# Spectacle_Button_Board.net
KiCad netlist of a schematic drawn in EAGLE
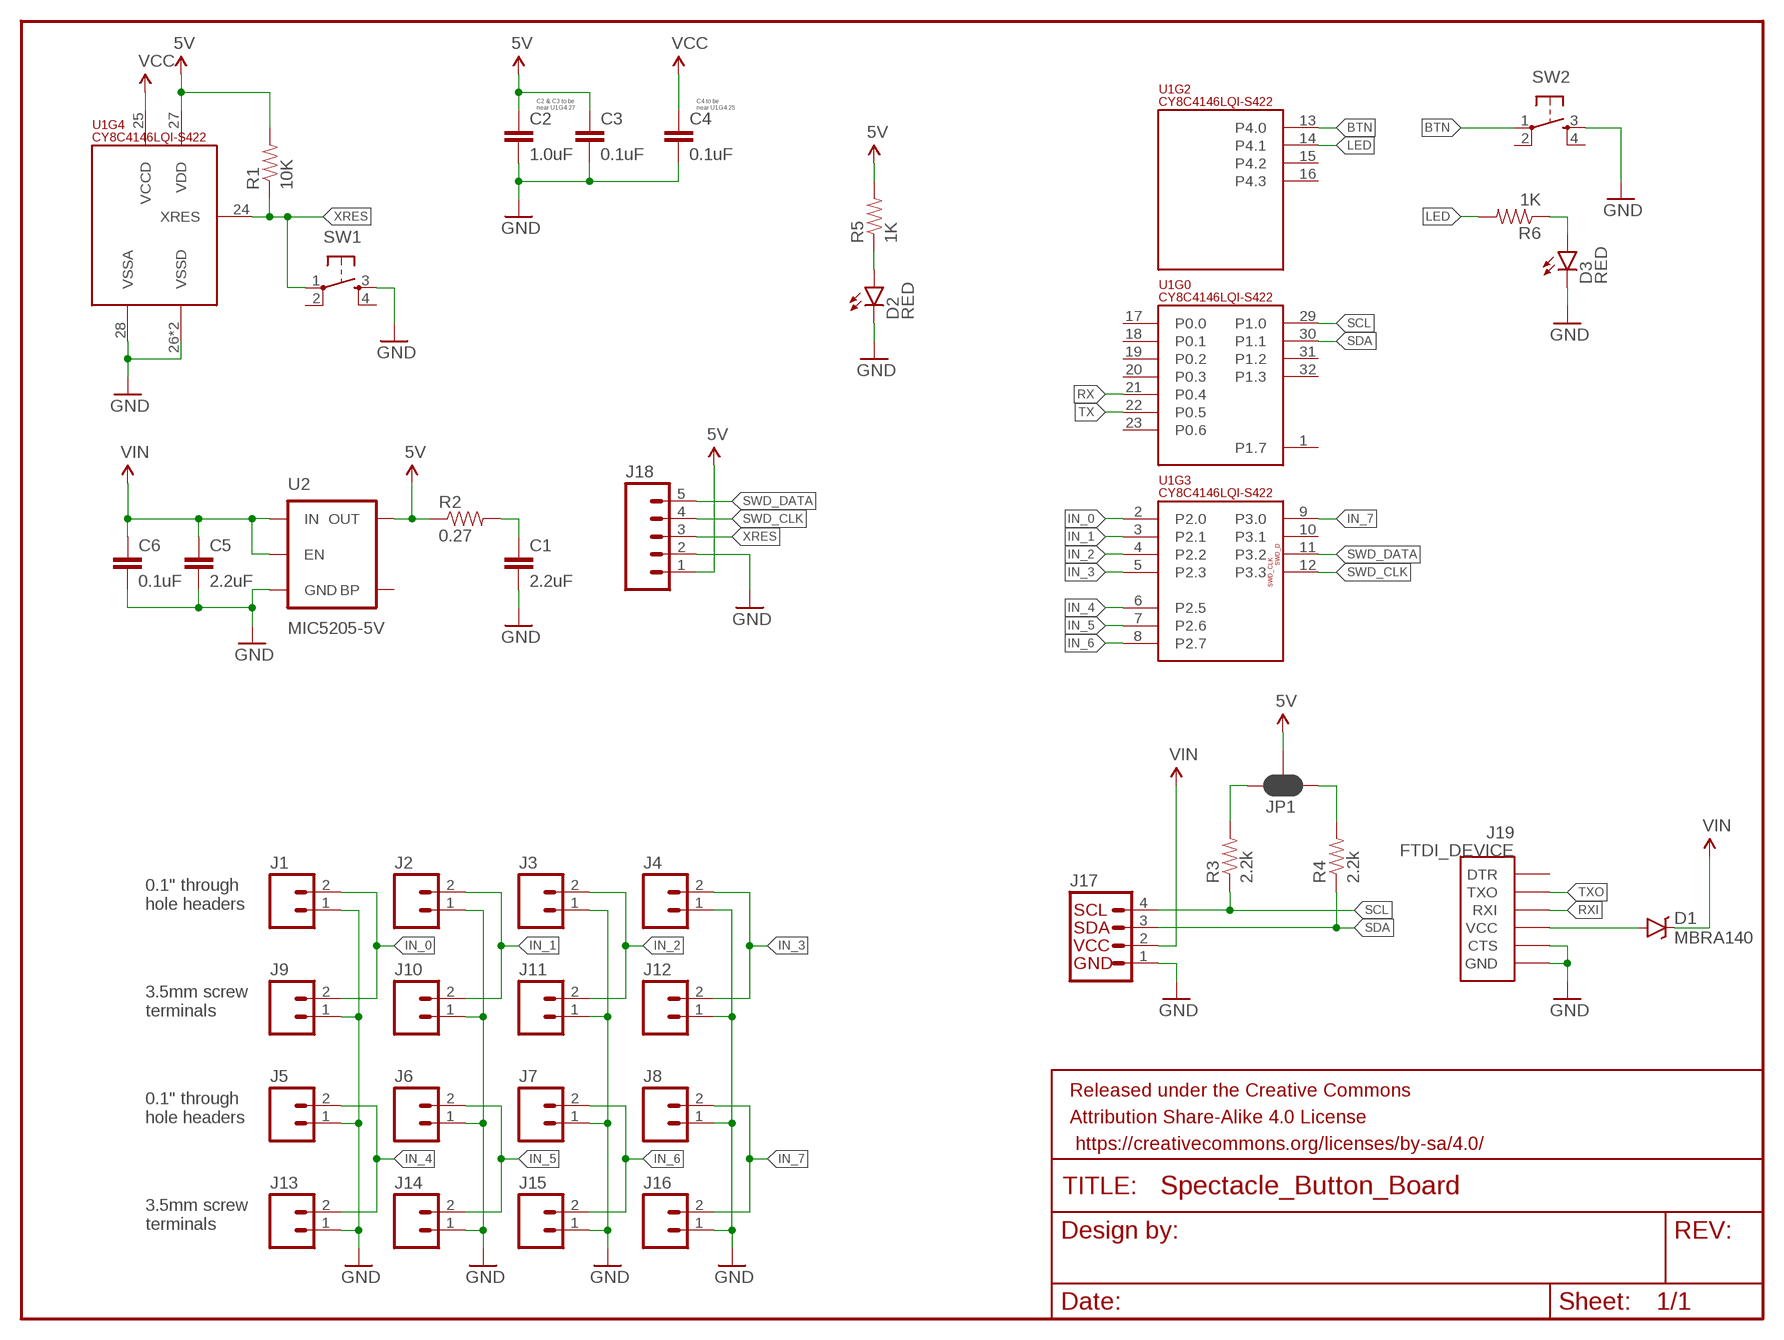
[diagram p0: schematic, sheet 1]

(export (version "E")
  (design (tool "Eeschema 10.0.6"))
  (components
    (comp (ref "C1")
      (value "2.2uF")
      (footprint "eagle-import:0603-CAP")
      (libsource (lib "eagle-import") (part "2.2UF-10V-20%(0603)"))
    )
    (comp (ref "C2")
      (value "1.0uF")
      (footprint "eagle-import:0402-CAP")
      (libsource (lib "eagle-import") (part "1.0UF-16V-10%(0402)"))
    )
    (comp (ref "C3")
      (value "0.1uF")
      (footprint "eagle-import:0402-CAP")
      (libsource (lib "eagle-import") (part "0.1UF-16V(+-10%)(0402)"))
    )
    (comp (ref "C4")
      (value "0.1uF")
      (footprint "eagle-import:0402-CAP")
      (libsource (lib "eagle-import") (part "0.1UF-16V(+-10%)(0402)"))
    )
    (comp (ref "C5")
      (value "2.2uF")
      (footprint "eagle-import:0603-CAP")
      (libsource (lib "eagle-import") (part "2.2UF-10V-20%(0603)"))
    )
    (comp (ref "C6")
      (value "0.1uF")
      (footprint "eagle-import:0402-CAP")
      (libsource (lib "eagle-import") (part "0.1UF-16V(+-10%)(0402)"))
    )
    (comp (ref "D1")
      (value "MBRA140")
      (footprint "eagle-import:SMA-DIODE")
      (libsource (lib "eagle-import") (part "DIODE-SCHOTTKY-MBRA140"))
    )
    (comp (ref "D2")
      (value "RED")
      (footprint "eagle-import:LED-0603")
      (libsource (lib "eagle-import") (part "LED-RED0603"))
    )
    (comp (ref "D3")
      (value "RED")
      (footprint "eagle-import:LED-0603")
      (libsource (lib "eagle-import") (part "LED-RED0603"))
    )
    (comp (ref "FRAME1")
      (value "FRAME-LETTER")
      (footprint "eagle-import:CREATIVE_COMMONS")
      (libsource (lib "eagle-import") (part "FRAME-LETTER"))
    )
    (comp (ref "J1")
      (value "M02PTH")
      (footprint "eagle-import:1X02")
      (libsource (lib "eagle-import") (part "M02PTH"))
    )
    (comp (ref "J2")
      (value "M02PTH")
      (footprint "eagle-import:1X02")
      (libsource (lib "eagle-import") (part "M02PTH"))
    )
    (comp (ref "J3")
      (value "M02PTH")
      (footprint "eagle-import:1X02")
      (libsource (lib "eagle-import") (part "M02PTH"))
    )
    (comp (ref "J4")
      (value "M02PTH")
      (footprint "eagle-import:1X02")
      (libsource (lib "eagle-import") (part "M02PTH"))
    )
    (comp (ref "J5")
      (value "M02PTH")
      (footprint "eagle-import:1X02")
      (libsource (lib "eagle-import") (part "M02PTH"))
    )
    (comp (ref "J6")
      (value "M02PTH")
      (footprint "eagle-import:1X02")
      (libsource (lib "eagle-import") (part "M02PTH"))
    )
    (comp (ref "J7")
      (value "M02PTH")
      (footprint "eagle-import:1X02")
      (libsource (lib "eagle-import") (part "M02PTH"))
    )
    (comp (ref "J8")
      (value "M02PTH")
      (footprint "eagle-import:1X02")
      (libsource (lib "eagle-import") (part "M02PTH"))
    )
    (comp (ref "J9")
      (value "M023.5MM_LOCK")
      (footprint "eagle-import:SCREWTERMINAL-3.5MM-2_LOCK")
      (libsource (lib "eagle-import") (part "M023.5MM_LOCK"))
    )
    (comp (ref "J10")
      (value "M023.5MM_LOCK")
      (footprint "eagle-import:SCREWTERMINAL-3.5MM-2_LOCK")
      (libsource (lib "eagle-import") (part "M023.5MM_LOCK"))
    )
    (comp (ref "J11")
      (value "M023.5MM_LOCK")
      (footprint "eagle-import:SCREWTERMINAL-3.5MM-2_LOCK")
      (libsource (lib "eagle-import") (part "M023.5MM_LOCK"))
    )
    (comp (ref "J12")
      (value "M023.5MM_LOCK")
      (footprint "eagle-import:SCREWTERMINAL-3.5MM-2_LOCK")
      (libsource (lib "eagle-import") (part "M023.5MM_LOCK"))
    )
    (comp (ref "J13")
      (value "M023.5MM_LOCK")
      (footprint "eagle-import:SCREWTERMINAL-3.5MM-2_LOCK")
      (libsource (lib "eagle-import") (part "M023.5MM_LOCK"))
    )
    (comp (ref "J14")
      (value "M023.5MM_LOCK")
      (footprint "eagle-import:SCREWTERMINAL-3.5MM-2_LOCK")
      (libsource (lib "eagle-import") (part "M023.5MM_LOCK"))
    )
    (comp (ref "J15")
      (value "M023.5MM_LOCK")
      (footprint "eagle-import:SCREWTERMINAL-3.5MM-2_LOCK")
      (libsource (lib "eagle-import") (part "M023.5MM_LOCK"))
    )
    (comp (ref "J16")
      (value "M023.5MM_LOCK")
      (footprint "eagle-import:SCREWTERMINAL-3.5MM-2_LOCK")
      (libsource (lib "eagle-import") (part "M023.5MM_LOCK"))
    )
    (comp (ref "J17")
      (value "I2C_STANDARD")
      (footprint "eagle-import:1X04")
      (libsource (lib "eagle-import") (part "I2C_STANDARD"))
    )
    (comp (ref "J18")
      (value "M05PTH")
      (footprint "eagle-import:1X05")
      (libsource (lib "eagle-import") (part "M05PTH"))
    )
    (comp (ref "J19")
      (value "FTDI_DEVICE")
      (footprint "eagle-import:FTDI_DEVICE_SIDE")
      (libsource (lib "eagle-import") (part "FTDI_DEVICE"))
    )
    (comp (ref "JP1")
      (value "JUMPER-PAD-3-NC_BY_PASTE")
      (footprint "eagle-import:PAD-JUMPER-3-NC_BY_PASTE_YES_SILK_FULL_BOX")
      (libsource (lib "eagle-import") (part "JUMPER-PAD-3-NC_BY_PASTE"))
    )
    (comp (ref "R1")
      (value "10K")
      (footprint "eagle-import:0603-RES")
      (libsource (lib "eagle-import") (part "10KOHM-1/10W-1%(0603)0603"))
    )
    (comp (ref "R2")
      (value "0.27")
      (footprint "eagle-import:0603-RES")
      (libsource (lib "eagle-import") (part "0.27OHM-1/10W-1%(0603)"))
    )
    (comp (ref "R3")
      (value "2.2k")
      (footprint "eagle-import:0603-RES")
      (libsource (lib "eagle-import") (part "2.2KOHM-1/10W-1%(0603)"))
    )
    (comp (ref "R4")
      (value "2.2k")
      (footprint "eagle-import:0603-RES")
      (libsource (lib "eagle-import") (part "2.2KOHM-1/10W-1%(0603)"))
    )
    (comp (ref "R5")
      (value "1K")
      (footprint "eagle-import:0603-RES")
      (libsource (lib "eagle-import") (part "1KOHM-1/10W-1%(0603)"))
    )
    (comp (ref "R6")
      (value "1K")
      (footprint "eagle-import:0603-RES")
      (libsource (lib "eagle-import") (part "1KOHM-1/10W-1%(0603)"))
    )
    (comp (ref "SW1")
      (value "SWITCH_SPST_4_PINRECT")
      (footprint "eagle-import:TACTILE_SWITCH_SMD_4.6X2.8MM")
      (libsource (lib "eagle-import") (part "SWITCH_SPST_4_PINRECT"))
    )
    (comp (ref "SW2")
      (value "SWITCH_SPST_4_PINRECT")
      (footprint "eagle-import:TACTILE_SWITCH_SMD_4.6X2.8MM")
      (libsource (lib "eagle-import") (part "SWITCH_SPST_4_PINRECT"))
    )
    (comp (ref "U1")
      (value "CY8C4146LQI-S422")
      (footprint "eagle-import:QFN-32")
      (libsource (lib "eagle-import") (part "PSOC4_4100S_32QFN"))
    )
    (comp (ref "U2")
      (value "MIC5205-5V")
      (footprint "eagle-import:SOT23-5")
      (libsource (lib "eagle-import") (part "V_REG_MIC52055V"))
    )
  )
  (nets
    (net (code "1") (name "5V") (class "Default")
      (node (ref "C2") (pin "1") (pinfunction "1_1") (pintype "passive"))
      (node (ref "C3") (pin "1") (pinfunction "1_1") (pintype "passive"))
      (node (ref "J18") (pin "1") (pinfunction "1_1") (pintype "passive"))
      (node (ref "JP1") (pin "2") (pinfunction "2_2") (pintype "passive"))
      (node (ref "R1") (pin "2") (pinfunction "2_2") (pintype "passive"))
      (node (ref "R2") (pin "1") (pinfunction "1_1") (pintype "passive"))
      (node (ref "R5") (pin "2") (pinfunction "2_2") (pintype "passive"))
      (node (ref "U1") (pin "27") (pinfunction "VDD_27") (pintype "bidirectional"))
      (node (ref "U2") (pin "5") (pinfunction "OUT_5") (pintype "passive"))
    )
    (net (code "2") (name "BTN") (class "Default")
      (node (ref "SW2") (pin "1") (pinfunction "1_1") (pintype "passive"))
      (node (ref "U1") (pin "13") (pinfunction "P4.0_13") (pintype "bidirectional"))
    )
    (net (code "3") (name "GND") (class "Default")
      (node (ref "C1") (pin "2") (pinfunction "2_2") (pintype "passive"))
      (node (ref "C2") (pin "2") (pinfunction "2_2") (pintype "passive"))
      (node (ref "C3") (pin "2") (pinfunction "2_2") (pintype "passive"))
      (node (ref "C4") (pin "2") (pinfunction "2_2") (pintype "passive"))
      (node (ref "C5") (pin "2") (pinfunction "2_2") (pintype "passive"))
      (node (ref "C6") (pin "2") (pinfunction "2_2") (pintype "passive"))
      (node (ref "D2") (pin "C") (pinfunction "C_C") (pintype "passive"))
      (node (ref "D3") (pin "C") (pinfunction "C_C") (pintype "passive"))
      (node (ref "J1") (pin "1") (pinfunction "1_1") (pintype "passive"))
      (node (ref "J10") (pin "1") (pinfunction "1_1") (pintype "passive"))
      (node (ref "J11") (pin "1") (pinfunction "1_1") (pintype "passive"))
      (node (ref "J12") (pin "1") (pinfunction "1_1") (pintype "passive"))
      (node (ref "J13") (pin "1") (pinfunction "1_1") (pintype "passive"))
      (node (ref "J14") (pin "1") (pinfunction "1_1") (pintype "passive"))
      (node (ref "J15") (pin "1") (pinfunction "1_1") (pintype "passive"))
      (node (ref "J16") (pin "1") (pinfunction "1_1") (pintype "passive"))
      (node (ref "J17") (pin "1") (pinfunction "1_1") (pintype "passive"))
      (node (ref "J18") (pin "2") (pinfunction "2_2") (pintype "passive"))
      (node (ref "J19") (pin "P$5") (pinfunction "CTS_P$5") (pintype "bidirectional"))
      (node (ref "J19") (pin "P$6") (pinfunction "GND_P$6") (pintype "bidirectional"))
      (node (ref "J2") (pin "1") (pinfunction "1_1") (pintype "passive"))
      (node (ref "J3") (pin "1") (pinfunction "1_1") (pintype "passive"))
      (node (ref "J4") (pin "1") (pinfunction "1_1") (pintype "passive"))
      (node (ref "J5") (pin "1") (pinfunction "1_1") (pintype "passive"))
      (node (ref "J6") (pin "1") (pinfunction "1_1") (pintype "passive"))
      (node (ref "J7") (pin "1") (pinfunction "1_1") (pintype "passive"))
      (node (ref "J8") (pin "1") (pinfunction "1_1") (pintype "passive"))
      (node (ref "J9") (pin "1") (pinfunction "1_1") (pintype "passive"))
      (node (ref "SW1") (pin "3") (pinfunction "3_3") (pintype "passive"))
      (node (ref "SW2") (pin "3") (pinfunction "3_3") (pintype "passive"))
      (node (ref "U1") (pin "26") (pinfunction "VSSD_26") (pintype "bidirectional"))
      (node (ref "U1") (pin "28") (pinfunction "VSSA_28") (pintype "bidirectional"))
      (node (ref "U1") (pin "EP") (pinfunction "VSSD_EP") (pintype "bidirectional"))
      (node (ref "U2") (pin "2") (pinfunction "GND_2") (pintype "input"))
    )
    (net (code "4") (name "IN_0") (class "Default")
      (node (ref "J1") (pin "2") (pinfunction "2_2") (pintype "passive"))
      (node (ref "J9") (pin "2") (pinfunction "2_2") (pintype "passive"))
      (node (ref "U1") (pin "2") (pinfunction "P2.0_2") (pintype "bidirectional"))
    )
    (net (code "5") (name "IN_1") (class "Default")
      (node (ref "J10") (pin "2") (pinfunction "2_2") (pintype "passive"))
      (node (ref "J2") (pin "2") (pinfunction "2_2") (pintype "passive"))
      (node (ref "U1") (pin "3") (pinfunction "P2.1_3") (pintype "bidirectional"))
    )
    (net (code "6") (name "IN_2") (class "Default")
      (node (ref "J11") (pin "2") (pinfunction "2_2") (pintype "passive"))
      (node (ref "J3") (pin "2") (pinfunction "2_2") (pintype "passive"))
      (node (ref "U1") (pin "4") (pinfunction "P2.2_4") (pintype "bidirectional"))
    )
    (net (code "7") (name "IN_3") (class "Default")
      (node (ref "J12") (pin "2") (pinfunction "2_2") (pintype "passive"))
      (node (ref "J4") (pin "2") (pinfunction "2_2") (pintype "passive"))
      (node (ref "U1") (pin "5") (pinfunction "P2.3_5") (pintype "bidirectional"))
    )
    (net (code "8") (name "IN_4") (class "Default")
      (node (ref "J13") (pin "2") (pinfunction "2_2") (pintype "passive"))
      (node (ref "J5") (pin "2") (pinfunction "2_2") (pintype "passive"))
      (node (ref "U1") (pin "6") (pinfunction "P2.5_6") (pintype "bidirectional"))
    )
    (net (code "9") (name "IN_5") (class "Default")
      (node (ref "J14") (pin "2") (pinfunction "2_2") (pintype "passive"))
      (node (ref "J6") (pin "2") (pinfunction "2_2") (pintype "passive"))
      (node (ref "U1") (pin "7") (pinfunction "P2.6_7") (pintype "bidirectional"))
    )
    (net (code "10") (name "IN_6") (class "Default")
      (node (ref "J15") (pin "2") (pinfunction "2_2") (pintype "passive"))
      (node (ref "J7") (pin "2") (pinfunction "2_2") (pintype "passive"))
      (node (ref "U1") (pin "8") (pinfunction "P2.7_8") (pintype "bidirectional"))
    )
    (net (code "11") (name "IN_7") (class "Default")
      (node (ref "J16") (pin "2") (pinfunction "2_2") (pintype "passive"))
      (node (ref "J8") (pin "2") (pinfunction "2_2") (pintype "passive"))
      (node (ref "U1") (pin "9") (pinfunction "P3.0_9") (pintype "bidirectional"))
    )
    (net (code "12") (name "LED") (class "Default")
      (node (ref "R6") (pin "2") (pinfunction "2_2") (pintype "passive"))
      (node (ref "U1") (pin "14") (pinfunction "P4.1_14") (pintype "bidirectional"))
    )
    (net (code "13") (name "Net-(C1-Pad1)") (class "Default")
      (node (ref "C1") (pin "1") (pinfunction "1_1") (pintype "passive"))
      (node (ref "R2") (pin "2") (pinfunction "2_2") (pintype "passive"))
    )
    (net (code "14") (name "Net-(D2-PadA)") (class "Default")
      (node (ref "D2") (pin "A") (pinfunction "A_A") (pintype "passive"))
      (node (ref "R5") (pin "1") (pinfunction "1_1") (pintype "passive"))
    )
    (net (code "15") (name "Net-(D3-PadA)") (class "Default")
      (node (ref "D3") (pin "A") (pinfunction "A_A") (pintype "passive"))
      (node (ref "R6") (pin "1") (pinfunction "1_1") (pintype "passive"))
    )
    (net (code "16") (name "Net-(J19-VCC)") (class "Default")
      (node (ref "D1") (pin "A") (pinfunction "A_A") (pintype "passive"))
      (node (ref "J19") (pin "P$4") (pinfunction "VCC_P$4") (pintype "bidirectional"))
    )
    (net (code "17") (name "Net-(JP1-Pad1)") (class "Default")
      (node (ref "JP1") (pin "1") (pinfunction "1_1") (pintype "passive"))
      (node (ref "R4") (pin "2") (pinfunction "2_2") (pintype "passive"))
    )
    (net (code "18") (name "Net-(JP1-Pad3)") (class "Default")
      (node (ref "JP1") (pin "3") (pinfunction "3_3") (pintype "passive"))
      (node (ref "R3") (pin "2") (pinfunction "2_2") (pintype "passive"))
    )
    (net (code "19") (name "RX") (class "Default")
      (node (ref "U1") (pin "21") (pinfunction "P0.4_21") (pintype "bidirectional"))
    )
    (net (code "20") (name "RXI") (class "Default")
      (node (ref "J19") (pin "P$3") (pinfunction "RXI_P$3") (pintype "bidirectional"))
    )
    (net (code "21") (name "SCL") (class "Default")
      (node (ref "J17") (pin "4") (pinfunction "4_4") (pintype "passive"))
      (node (ref "R3") (pin "1") (pinfunction "1_1") (pintype "passive"))
      (node (ref "U1") (pin "29") (pinfunction "P1.0_29") (pintype "bidirectional"))
    )
    (net (code "22") (name "SDA") (class "Default")
      (node (ref "J17") (pin "3") (pinfunction "3_3") (pintype "passive"))
      (node (ref "R4") (pin "1") (pinfunction "1_1") (pintype "passive"))
      (node (ref "U1") (pin "30") (pinfunction "P1.1_30") (pintype "bidirectional"))
    )
    (net (code "23") (name "SWD_CLK") (class "Default")
      (node (ref "J18") (pin "4") (pinfunction "4_4") (pintype "passive"))
      (node (ref "U1") (pin "12") (pinfunction "P3.3_12") (pintype "bidirectional"))
    )
    (net (code "24") (name "SWD_DATA") (class "Default")
      (node (ref "J18") (pin "5") (pinfunction "5_5") (pintype "passive"))
      (node (ref "U1") (pin "11") (pinfunction "P3.2_11") (pintype "bidirectional"))
    )
    (net (code "25") (name "TX") (class "Default")
      (node (ref "U1") (pin "22") (pinfunction "P0.5_22") (pintype "bidirectional"))
    )
    (net (code "26") (name "TXO") (class "Default")
      (node (ref "J19") (pin "P$2") (pinfunction "TXO_P$2") (pintype "bidirectional"))
    )
    (net (code "27") (name "VCC") (class "Default")
      (node (ref "C4") (pin "1") (pinfunction "1_1") (pintype "passive"))
      (node (ref "U1") (pin "25") (pinfunction "VCCD_25") (pintype "bidirectional"))
    )
    (net (code "28") (name "VIN") (class "Default")
      (node (ref "C5") (pin "1") (pinfunction "1_1") (pintype "passive"))
      (node (ref "C6") (pin "1") (pinfunction "1_1") (pintype "passive"))
      (node (ref "D1") (pin "C") (pinfunction "C_C") (pintype "passive"))
      (node (ref "J17") (pin "2") (pinfunction "2_2") (pintype "passive"))
      (node (ref "U2") (pin "1") (pinfunction "IN_1") (pintype "input"))
      (node (ref "U2") (pin "3") (pinfunction "EN_3") (pintype "input"))
    )
    (net (code "29") (name "XRES") (class "Default")
      (node (ref "J18") (pin "3") (pinfunction "3_3") (pintype "passive"))
      (node (ref "R1") (pin "1") (pinfunction "1_1") (pintype "passive"))
      (node (ref "SW1") (pin "1") (pinfunction "1_1") (pintype "passive"))
      (node (ref "U1") (pin "24") (pinfunction "XRES_24") (pintype "bidirectional"))
    )
    (net (code "30") (name "unconnected-(J19-DTR-PadP$1)") (class "Default")
      (node (ref "J19") (pin "P$1") (pinfunction "DTR_P$1") (pintype "bidirectional"))
    )
    (net (code "31") (name "unconnected-(SW1-Pad2)") (class "Default")
      (node (ref "SW1") (pin "2") (pinfunction "2_2") (pintype "passive"))
    )
    (net (code "32") (name "unconnected-(SW1-Pad4)") (class "Default")
      (node (ref "SW1") (pin "4") (pinfunction "4_4") (pintype "passive"))
    )
    (net (code "33") (name "unconnected-(SW2-Pad2)") (class "Default")
      (node (ref "SW2") (pin "2") (pinfunction "2_2") (pintype "passive"))
    )
    (net (code "34") (name "unconnected-(SW2-Pad4)") (class "Default")
      (node (ref "SW2") (pin "4") (pinfunction "4_4") (pintype "passive"))
    )
    (net (code "35") (name "unconnected-(U1A-P0.0-Pad17)") (class "Default")
      (node (ref "U1") (pin "17") (pinfunction "P0.0_17") (pintype "bidirectional"))
    )
    (net (code "36") (name "unconnected-(U1A-P0.1-Pad18)") (class "Default")
      (node (ref "U1") (pin "18") (pinfunction "P0.1_18") (pintype "bidirectional"))
    )
    (net (code "37") (name "unconnected-(U1A-P0.2-Pad19)") (class "Default")
      (node (ref "U1") (pin "19") (pinfunction "P0.2_19") (pintype "bidirectional"))
    )
    (net (code "38") (name "unconnected-(U1A-P0.3-Pad20)") (class "Default")
      (node (ref "U1") (pin "20") (pinfunction "P0.3_20") (pintype "bidirectional"))
    )
    (net (code "39") (name "unconnected-(U1A-P0.6-Pad23)") (class "Default")
      (node (ref "U1") (pin "23") (pinfunction "P0.6_23") (pintype "bidirectional"))
    )
    (net (code "40") (name "unconnected-(U1A-P1.2-Pad31)") (class "Default")
      (node (ref "U1") (pin "31") (pinfunction "P1.2_31") (pintype "bidirectional"))
    )
    (net (code "41") (name "unconnected-(U1A-P1.3-Pad32)") (class "Default")
      (node (ref "U1") (pin "32") (pinfunction "P1.3_32") (pintype "bidirectional"))
    )
    (net (code "42") (name "unconnected-(U1A-P1.7-Pad1)") (class "Default")
      (node (ref "U1") (pin "1") (pinfunction "P1.7_1") (pintype "bidirectional"))
    )
    (net (code "43") (name "unconnected-(U1B-P4.2-Pad15)") (class "Default")
      (node (ref "U1") (pin "15") (pinfunction "P4.2_15") (pintype "bidirectional"))
    )
    (net (code "44") (name "unconnected-(U1B-P4.3-Pad16)") (class "Default")
      (node (ref "U1") (pin "16") (pinfunction "P4.3_16") (pintype "bidirectional"))
    )
    (net (code "45") (name "unconnected-(U1C-P3.1-Pad10)") (class "Default")
      (node (ref "U1") (pin "10") (pinfunction "P3.1_10") (pintype "bidirectional"))
    )
    (net (code "46") (name "unconnected-(U2-BP-Pad4)") (class "Default")
      (node (ref "U2") (pin "4") (pinfunction "BP_4") (pintype "input"))
    )
  )
)
